# uC.net
KiCad netlist of a schematic drawn in Altium Designer
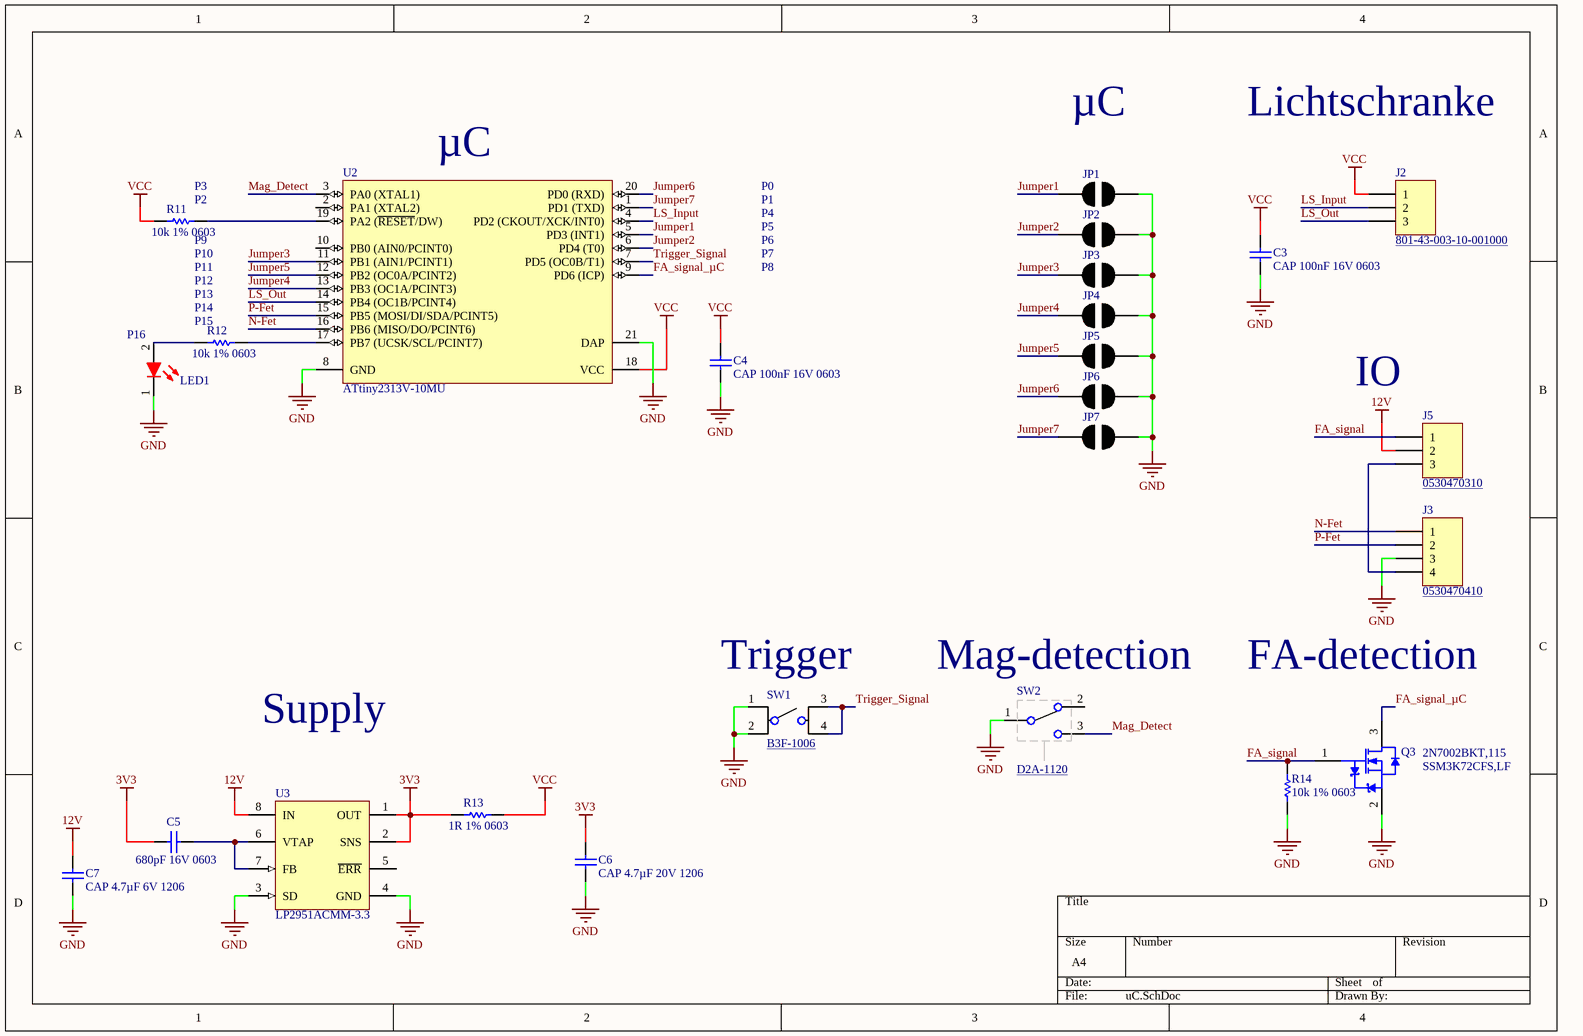
[diagram p0: uC.SchDoc]

(export (version "E")
  (design (tool "Eeschema 10.0.6"))
  (components
    (comp (ref "C3")
      (value "CAP 100nF 16V 0603")
      (footprint "CAPC0603(1608)100_N")
      (description "CAP 100nF 16V ±20% 0603 (1608 Metric) Thickness 1mm SMD")
      (fields (field (name "TOLERANCE") "Â±20%"))
      (libsource (lib "Altium Content Vault") (part "CMP-1035-02585-1"))
    )
    (comp (ref "C4")
      (value "CAP 100nF 16V 0603")
      (footprint "CAPC0603(1608)100_N")
      (description "CAP 100nF 16V ±20% 0603 (1608 Metric) Thickness 1mm SMD")
      (fields (field (name "TOLERANCE") "Â±20%"))
      (libsource (lib "Altium Content Vault") (part "CMP-1035-02585-1"))
    )
    (comp (ref "C5")
      (value "680pF 16V 0603")
      (footprint "CAPC0603(1608)100_L")
      (description "CAP 180pF 16V ±2% 0603 (1608 Metric) Thickness 1mm SMD")
      (fields (field (name "TOLERANCE") "Â±2%"))
      (libsource (lib "Altium Content Vault") (part "CAP"))
    )
    (comp (ref "C6")
      (value "CAP 4.7µF 20V 1206")
      (footprint "CAPC1206(3216)190_M")
      (description "CAP 100nF 25V ±5% 1206 (3216 Metric) Thickness 1.9mm SMD")
      (fields (field (name "TOLERANCE") "Â±5%"))
      (libsource (lib "Altium Content Vault") (part "CAP"))
    )
    (comp (ref "C7")
      (value "CAP 4.7µF 6V 1206")
      (footprint "CAPC1206(3216)190_M")
      (description "CAP 100nF 25V ±5% 1206 (3216 Metric) Thickness 1.9mm SMD")
      (fields (field (name "TOLERANCE") "Â±5%"))
      (libsource (lib "Altium Content Vault") (part "CAP"))
    )
    (comp (ref "J2")
      (value "801-43-003-10-001000")
      (footprint "801-43-003-10-001000")
      (description "3 Pim header socket 7mm height")
      (libsource (lib "Connector") (part "801-43-003-10-001000"))
    )
    (comp (ref "J3")
      (value "0530470410")
      (footprint "530470410")
      (description "Molex Picoblade, 4Pin THT Straight")
      (libsource (lib "Connector") (part "0530470410"))
    )
    (comp (ref "J5")
      (value "0530470310")
      (footprint "530470310")
      (description "Molex Picoblade, 3Pin THT Straight")
      (libsource (lib "Connector") (part "0530470310"))
    )
    (comp (ref "JP1")
      (value "Jumperpads")
      (footprint "Jumper")
      (libsource (lib "Connector") (part "Jumperpads"))
    )
    (comp (ref "JP2")
      (value "Jumperpads")
      (footprint "Jumper")
      (libsource (lib "Connector") (part "Jumperpads"))
    )
    (comp (ref "JP3")
      (value "Jumperpads")
      (footprint "Jumper")
      (libsource (lib "Connector") (part "Jumperpads"))
    )
    (comp (ref "JP4")
      (value "Jumperpads")
      (footprint "Jumper")
      (libsource (lib "Connector") (part "Jumperpads"))
    )
    (comp (ref "JP5")
      (value "Jumperpads")
      (footprint "Jumper")
      (libsource (lib "Connector") (part "Jumperpads"))
    )
    (comp (ref "JP6")
      (value "Jumperpads")
      (footprint "Jumper")
      (libsource (lib "Connector") (part "Jumperpads"))
    )
    (comp (ref "JP7")
      (value "Jumperpads")
      (footprint "Jumper")
      (libsource (lib "Connector") (part "Jumperpads"))
    )
    (comp (ref "LED1")
      (value "~")
      (footprint "WE-LED-0603_RD_N")
      (description "Chip LED 0603 red")
      (libsource (lib "LEDs") (part "LED_0603_RD"))
    )
    (comp (ref "Q3")
      (value "2N7002BKT,115")
      (footprint "NXP-SOT416_B_N")
      (description "N-Channel Trench MOSFET, 60 V, 0.29 A, -55 to 150 degC, 3-Pin SOT416, Tape and Reel")
      (fields (field (name "MANUFACTURER") "NXP Semiconductors"))
      (libsource (lib "Altium Content Vault") (part "NXP-NMOS-GSD-3_A"))
    )
    (comp (ref "R11")
      (value "10k 1% 0603")
      (footprint "RESC0603(1608)_M")
      (description "2R8 0.1W 1% 0603 (1608 Metric)  SMD")
      (fields (field (name "POWER") "0.1 W") (field (name "TOLERANCE") "1 %"))
      (libsource (lib "Altium Content Vault") (part "CMP-1012-00220-1"))
    )
    (comp (ref "R12")
      (value "10k 1% 0603")
      (footprint "RESC0603(1608)_M")
      (description "2R8 0.1W 1% 0603 (1608 Metric)  SMD")
      (fields (field (name "POWER") "0.1 W") (field (name "TOLERANCE") "1 %"))
      (libsource (lib "Altium Content Vault") (part "CMP-1012-00220-1"))
    )
    (comp (ref "R13")
      (value "1R 1% 0603")
      (footprint "RESC0603(1608)_M")
      (description "2R8 0.1W 1% 0603 (1608 Metric)  SMD")
      (fields (field (name "POWER") "0.1 W") (field (name "TOLERANCE") "1 %"))
      (libsource (lib "Altium Content Vault") (part "RES"))
    )
    (comp (ref "R14")
      (value "10k 1% 0603")
      (footprint "RESC0603(1608)_M")
      (description "2R8 0.1W 1% 0603 (1608 Metric)  SMD")
      (fields (field (name "POWER") "0.1 W") (field (name "TOLERANCE") "1 %"))
      (libsource (lib "Altium Content Vault") (part "CMP-1012-00220-1"))
    )
    (comp (ref "SW1")
      (value "B3F-1006")
      (footprint "OMRON B3F-1006")
      (description "Tactile Switch Omron B3F-1006")
      (libsource (lib "Switch") (part "B3F-1006"))
    )
    (comp (ref "SW2")
      (value "D2A-1120")
      (footprint "D2A-1120")
      (description "SWITCH TACTILE Omron D2A 0.1A 30V")
      (fields (field (name "MANUFACTURER") "Omron") (field (name "MANUFACTURER PART") "MK-12C02-PB"))
      (libsource (lib "Switch") (part "D2A-1120"))
    )
    (comp (ref "U2")
      (value "ATtiny2313V-10MU")
      (footprint "20M1_M")
      (libsource (lib "Altium Content Vault") (part "CMP-0093-00093-2"))
    )
    (comp (ref "U3")
      (value "LP2951ACMM-3.3")
      (footprint "DGK0008A_N")
      (description "Series of Adjustable Micropower Voltage Regulators, 8-pin Mini SOIC")
      (fields (field (name "MANUFACTURER") "Texas Instruments"))
      (libsource (lib "Altium Content Vault") (part "CMP-0062-02229-3"))
    )
  )
  (nets
    (net (code "1") (name "/FA_signal") (class "Default")
      (node (ref "J5") (pin "1") (pinfunction "1_1") (pintype "passive"))
      (node (ref "Q3") (pin "1") (pinfunction "G_1") (pintype "passive"))
      (node (ref "R14") (pin "2") (pinfunction "2_2") (pintype "passive"))
    )
    (net (code "2") (name "/FA_signal_µC") (class "Default")
      (node (ref "Q3") (pin "3") (pinfunction "D_3") (pintype "passive"))
      (node (ref "U2") (pin "9") (pinfunction "PD6_(ICP)_9") (pintype "bidirectional"))
    )
    (net (code "3") (name "/Jumper1") (class "Default")
      (node (ref "JP1") (pin "1") (pinfunction "1_1") (pintype "passive"))
      (node (ref "U2") (pin "5") (pinfunction "PD3_(INT1)_5") (pintype "bidirectional"))
    )
    (net (code "4") (name "/Jumper2") (class "Default")
      (node (ref "JP2") (pin "1") (pinfunction "1_1") (pintype "passive"))
      (node (ref "U2") (pin "6") (pinfunction "PD4_(T0)_6") (pintype "bidirectional"))
    )
    (net (code "5") (name "/Jumper3") (class "Default")
      (node (ref "JP3") (pin "1") (pinfunction "1_1") (pintype "passive"))
      (node (ref "U2") (pin "11") (pinfunction "PB1_(AIN1/PCINT1)_11") (pintype "bidirectional"))
    )
    (net (code "6") (name "/Jumper4") (class "Default")
      (node (ref "JP4") (pin "1") (pinfunction "1_1") (pintype "passive"))
      (node (ref "U2") (pin "13") (pinfunction "PB3_(OC1A/PCINT3)_13") (pintype "bidirectional"))
    )
    (net (code "7") (name "/Jumper5") (class "Default")
      (node (ref "JP5") (pin "1") (pinfunction "1_1") (pintype "passive"))
      (node (ref "U2") (pin "12") (pinfunction "PB2_(OC0A/PCINT2)_12") (pintype "bidirectional"))
    )
    (net (code "8") (name "/Jumper6") (class "Default")
      (node (ref "JP6") (pin "1") (pinfunction "1_1") (pintype "passive"))
      (node (ref "U2") (pin "20") (pinfunction "PD0_(RXD)_20") (pintype "bidirectional"))
    )
    (net (code "9") (name "/Jumper7") (class "Default")
      (node (ref "JP7") (pin "1") (pinfunction "1_1") (pintype "passive"))
      (node (ref "U2") (pin "1") (pinfunction "PD1_(TXD)_1") (pintype "bidirectional"))
    )
    (net (code "10") (name "/LS_Input") (class "Default")
      (node (ref "J2") (pin "2") (pinfunction "2_2") (pintype "passive"))
      (node (ref "U2") (pin "4") (pinfunction "PD2_(CKOUT/XCK/INT0)_4") (pintype "bidirectional"))
    )
    (net (code "11") (name "/LS_Out") (class "Default")
      (node (ref "J2") (pin "3") (pinfunction "3_3") (pintype "passive"))
      (node (ref "U2") (pin "14") (pinfunction "PB4_(OC1B/PCINT4)_14") (pintype "bidirectional"))
    )
    (net (code "12") (name "/Mag_Detect") (class "Default")
      (node (ref "SW2") (pin "3") (pinfunction "NO_3") (pintype "passive"))
      (node (ref "U2") (pin "3") (pinfunction "PA0_(XTAL1)_3") (pintype "bidirectional"))
    )
    (net (code "13") (name "/N-Fet") (class "Default")
      (node (ref "J3") (pin "1") (pinfunction "1_1") (pintype "passive"))
      (node (ref "U2") (pin "16") (pinfunction "PB6_(MISO/DO/PCINT6)_16") (pintype "bidirectional"))
    )
    (net (code "14") (name "/P-Fet") (class "Default")
      (node (ref "J3") (pin "2") (pinfunction "2_2") (pintype "passive"))
      (node (ref "U2") (pin "15") (pinfunction "PB5_(MOSI/DI/SDA/PCINT5)_15") (pintype "bidirectional"))
    )
    (net (code "15") (name "/Trigger_Signal") (class "Default")
      (node (ref "SW1") (pin "3") (pinfunction "OUT_3") (pintype "passive"))
      (node (ref "SW1") (pin "4") (pinfunction "OUT_4") (pintype "passive"))
      (node (ref "U2") (pin "7") (pinfunction "PD5_(OC0B/T1)_7") (pintype "bidirectional"))
    )
    (net (code "16") (name "3V3") (class "Default")
      (node (ref "C5") (pin "1") (pinfunction "1_1") (pintype "passive"))
      (node (ref "C6") (pin "2") (pinfunction "2_2") (pintype "passive"))
      (node (ref "R13") (pin "1") (pinfunction "1_1") (pintype "passive"))
      (node (ref "U3") (pin "1") (pinfunction "OUT_1") (pintype "power_in"))
      (node (ref "U3") (pin "2") (pinfunction "SNS_2") (pintype "passive"))
    )
    (net (code "17") (name "12V") (class "Default")
      (node (ref "C7") (pin "1") (pinfunction "1_1") (pintype "passive"))
      (node (ref "J5") (pin "2") (pinfunction "2_2") (pintype "passive"))
      (node (ref "U3") (pin "8") (pinfunction "IN_8") (pintype "power_in"))
    )
    (net (code "18") (name "GND") (class "Default")
      (node (ref "C3") (pin "1") (pinfunction "1_1") (pintype "passive"))
      (node (ref "C4") (pin "1") (pinfunction "1_1") (pintype "passive"))
      (node (ref "C6") (pin "1") (pinfunction "1_1") (pintype "passive"))
      (node (ref "C7") (pin "2") (pinfunction "2_2") (pintype "passive"))
      (node (ref "J3") (pin "3") (pinfunction "3_3") (pintype "passive"))
      (node (ref "JP1") (pin "2") (pinfunction "2_2") (pintype "passive"))
      (node (ref "JP2") (pin "2") (pinfunction "2_2") (pintype "passive"))
      (node (ref "JP3") (pin "2") (pinfunction "2_2") (pintype "passive"))
      (node (ref "JP4") (pin "2") (pinfunction "2_2") (pintype "passive"))
      (node (ref "JP5") (pin "2") (pinfunction "2_2") (pintype "passive"))
      (node (ref "JP6") (pin "2") (pinfunction "2_2") (pintype "passive"))
      (node (ref "JP7") (pin "2") (pinfunction "2_2") (pintype "passive"))
      (node (ref "LED1") (pin "1") (pinfunction "K_1") (pintype "passive"))
      (node (ref "Q3") (pin "2") (pinfunction "S_2") (pintype "passive"))
      (node (ref "R14") (pin "1") (pinfunction "1_1") (pintype "passive"))
      (node (ref "SW1") (pin "1") (pinfunction "IN_1") (pintype "passive"))
      (node (ref "SW1") (pin "2") (pinfunction "IN_2") (pintype "passive"))
      (node (ref "SW2") (pin "1") (pinfunction "COM_1") (pintype "passive"))
      (node (ref "U2") (pin "21") (pinfunction "DAP_21") (pintype "power_in"))
      (node (ref "U2") (pin "8") (pinfunction "GND_8") (pintype "power_in"))
      (node (ref "U3") (pin "3") (pinfunction "SD_3") (pintype "input"))
      (node (ref "U3") (pin "4") (pinfunction "GND_4") (pintype "power_in"))
    )
    (net (code "19") (name "Net-(J3-Pad4)") (class "Default")
      (node (ref "J3") (pin "4") (pinfunction "4_4") (pintype "passive"))
      (node (ref "J5") (pin "3") (pinfunction "3_3") (pintype "passive"))
    )
    (net (code "20") (name "Net-(LED1-A)") (class "Default")
      (node (ref "LED1") (pin "2") (pinfunction "A_2") (pintype "passive"))
      (node (ref "R12") (pin "1") (pinfunction "1_1") (pintype "passive"))
    )
    (net (code "21") (name "Net-(U2-PA2_(~{RESET}{slash}DW))") (class "Default")
      (node (ref "R11") (pin "2") (pinfunction "2_2") (pintype "passive"))
      (node (ref "U2") (pin "19") (pinfunction "PA2_(~{RESET}/DW)_19") (pintype "bidirectional"))
    )
    (net (code "22") (name "Net-(U2-PB7_(UCSK{slash}SCL{slash}PCINT7))") (class "Default")
      (node (ref "R12") (pin "2") (pinfunction "2_2") (pintype "passive"))
      (node (ref "U2") (pin "17") (pinfunction "PB7_(UCSK/SCL/PCINT7)_17") (pintype "bidirectional"))
    )
    (net (code "23") (name "Net-(U3-FB)") (class "Default")
      (node (ref "C5") (pin "2") (pinfunction "2_2") (pintype "passive"))
      (node (ref "U3") (pin "6") (pinfunction "VTAP_6") (pintype "passive"))
      (node (ref "U3") (pin "7") (pinfunction "FB_7") (pintype "input"))
    )
    (net (code "24") (name "VCC") (class "Default")
      (node (ref "C3") (pin "2") (pinfunction "2_2") (pintype "passive"))
      (node (ref "C4") (pin "2") (pinfunction "2_2") (pintype "passive"))
      (node (ref "J2") (pin "1") (pinfunction "1_1") (pintype "passive"))
      (node (ref "R11") (pin "1") (pinfunction "1_1") (pintype "passive"))
      (node (ref "R13") (pin "2") (pinfunction "2_2") (pintype "passive"))
      (node (ref "U2") (pin "18") (pinfunction "VCC_18") (pintype "power_in"))
    )
    (net (code "25") (name "unconnected-(SW2-NC-Pad2)") (class "Default")
      (node (ref "SW2") (pin "2") (pinfunction "NC_2") (pintype "passive"))
    )
    (net (code "26") (name "unconnected-(SW2-PadSH)") (class "Default")
      (node (ref "SW2") (pin "SH") (pinfunction "SH_SH") (pintype "passive"))
    )
    (net (code "27") (name "unconnected-(U2-PA1_(XTAL2)-Pad2)") (class "Default")
      (node (ref "U2") (pin "2") (pinfunction "PA1_(XTAL2)_2") (pintype "bidirectional"))
    )
    (net (code "28") (name "unconnected-(U2-PB0_(AIN0{slash}PCINT0)-Pad10)") (class "Default")
      (node (ref "U2") (pin "10") (pinfunction "PB0_(AIN0/PCINT0)_10") (pintype "bidirectional"))
    )
    (net (code "29") (name "unconnected-(U3-~{ERR}-Pad5)") (class "Default")
      (node (ref "U3") (pin "5") (pinfunction "~{ERR}_5") (pintype "open_collector"))
    )
  )
)
